# untitled.net
KiCad netlist of a schematic drawn in EAGLE
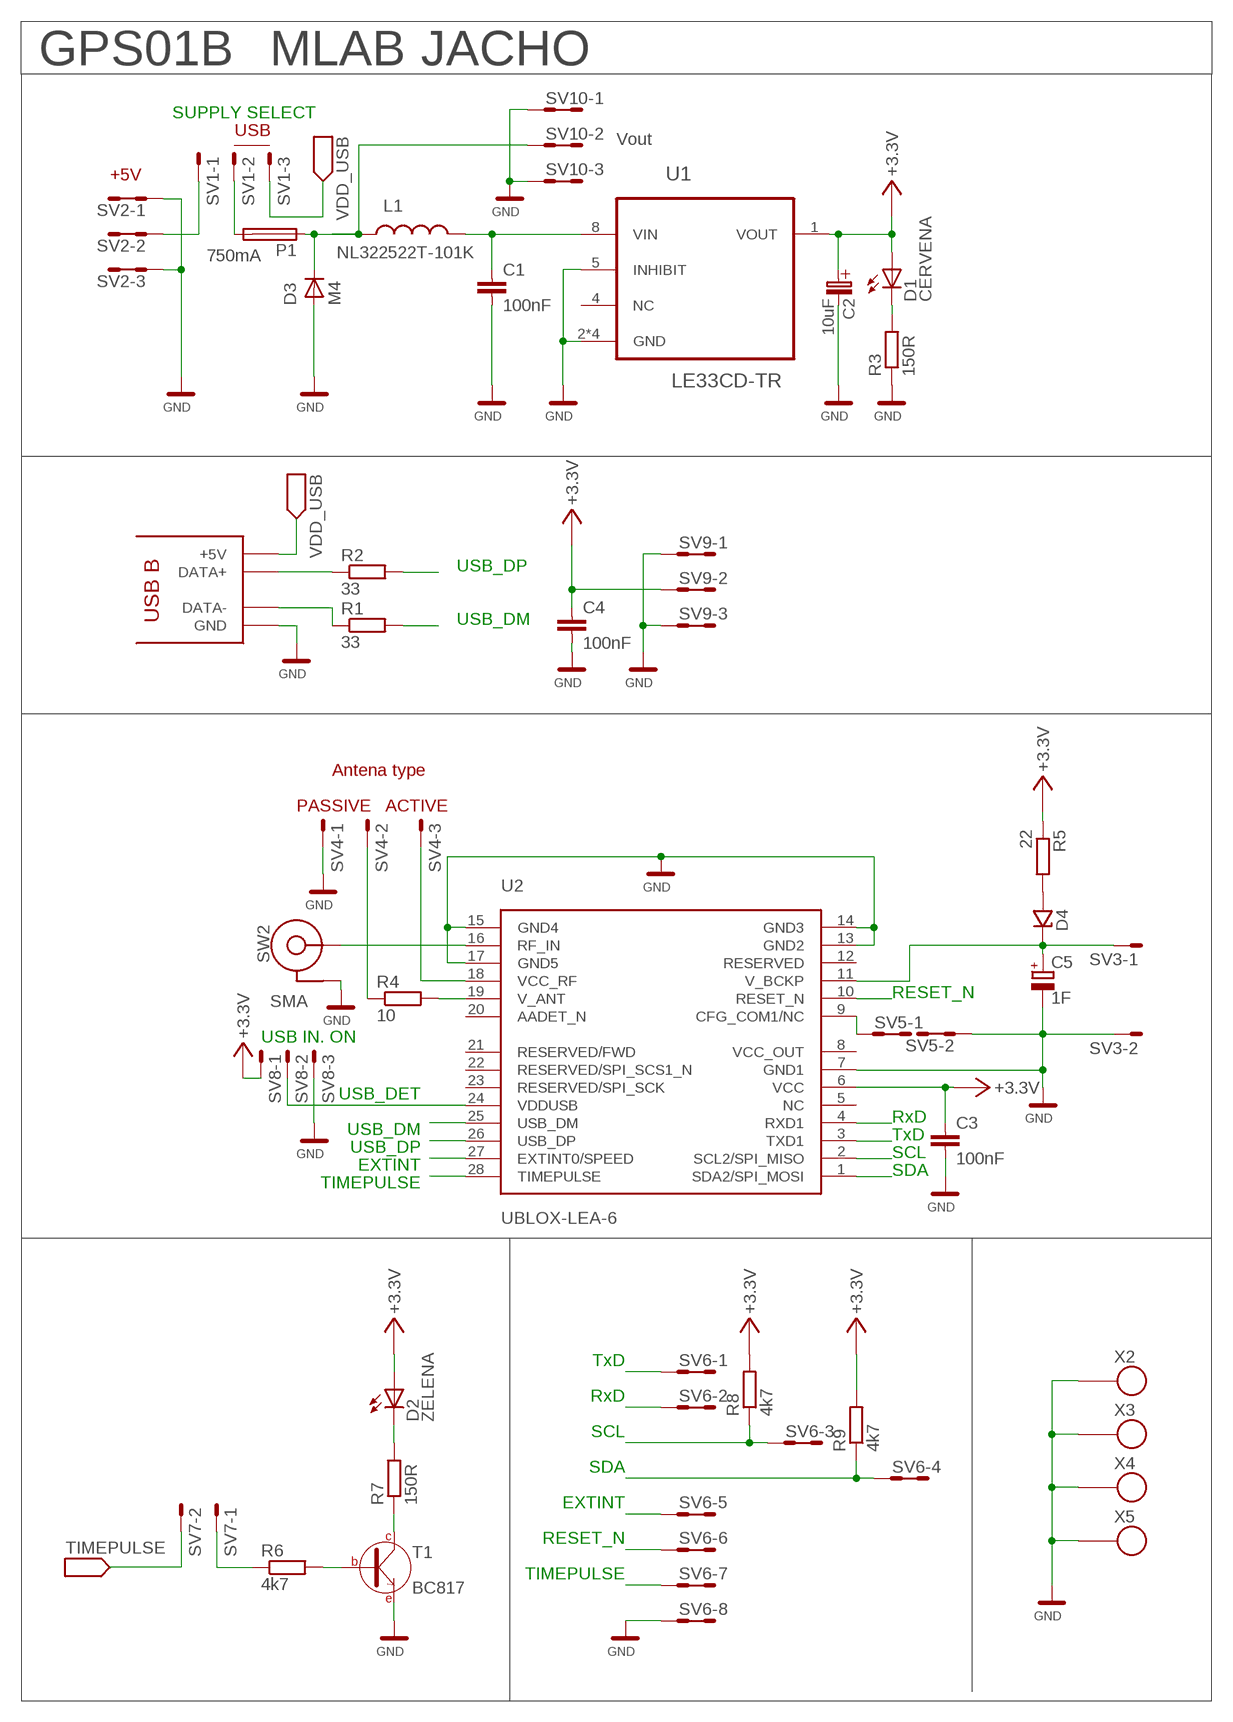
[diagram p0: schematic, sheet 1]

(export (version "E")
  (design (tool "Eeschema 10.0.6"))
  (components
    (comp (ref "C1")
      (value "100nF")
      (footprint "eagle-import:C0805")
      (libsource (lib "eagle-import") (part "C0805"))
    )
    (comp (ref "C2") (value "10uF") (footprint "eagle-import:B") (libsource (lib "eagle-import") (part "B")))
    (comp (ref "C3")
      (value "100nF")
      (footprint "eagle-import:C0805")
      (libsource (lib "eagle-import") (part "C0805"))
    )
    (comp (ref "C4")
      (value "100nF")
      (footprint "eagle-import:C0805")
      (libsource (lib "eagle-import") (part "C0805"))
    )
    (comp (ref "C5")
      (value "1F")
      (footprint "eagle-import:E3,5-8")
      (libsource (lib "eagle-import") (part "CPOL-EUE3.5-8"))
    )
    (comp (ref "D1")
      (value "CERVENA")
      (footprint "eagle-import:1206")
      (libsource (lib "eagle-import") (part "LED1206"))
    )
    (comp (ref "D2")
      (value "ZELENA")
      (footprint "eagle-import:1206")
      (libsource (lib "eagle-import") (part "LED1206"))
    )
    (comp (ref "D3")
      (value "M4")
      (footprint "eagle-import:SMA")
      (libsource (lib "eagle-import") (part "D-OB.SMA"))
    )
    (comp (ref "D4")
      (value "D-ZENEROVA")
      (footprint "eagle-import:MINIMELF")
      (libsource (lib "eagle-import") (part "D-ZENEROVA"))
    )
    (comp (ref "L1")
      (value "NL322522T-101K")
      (footprint "eagle-import:1210")
      (libsource (lib "eagle-import") (part "L1210"))
    )
    (comp (ref "P1")
      (value "750mA")
      (footprint "eagle-import:1812")
      (libsource (lib "eagle-import") (part "POJISTKA_1812"))
    )
    (comp (ref "R1")
      (value "33")
      (footprint "eagle-import:0805")
      (libsource (lib "eagle-import") (part "R0805"))
    )
    (comp (ref "R2")
      (value "33")
      (footprint "eagle-import:0805")
      (libsource (lib "eagle-import") (part "R0805"))
    )
    (comp (ref "R3")
      (value "150R")
      (footprint "eagle-import:0805")
      (libsource (lib "eagle-import") (part "R0805"))
    )
    (comp (ref "R4")
      (value "10")
      (footprint "eagle-import:0805")
      (libsource (lib "eagle-import") (part "R0805"))
    )
    (comp (ref "R5")
      (value "22")
      (footprint "eagle-import:0805")
      (libsource (lib "eagle-import") (part "R0805"))
    )
    (comp (ref "R6")
      (value "4k7")
      (footprint "eagle-import:0805")
      (libsource (lib "eagle-import") (part "R0805"))
    )
    (comp (ref "R7")
      (value "150R")
      (footprint "eagle-import:0805")
      (libsource (lib "eagle-import") (part "R0805"))
    )
    (comp (ref "R8")
      (value "4k7")
      (footprint "eagle-import:0805")
      (libsource (lib "eagle-import") (part "R0805"))
    )
    (comp (ref "R9")
      (value "4k7")
      (footprint "eagle-import:0805")
      (libsource (lib "eagle-import") (part "R0805"))
    )
    (comp (ref "SV1")
      (value "MA03-1")
      (footprint "eagle-import:MA03-1")
      (libsource (lib "eagle-import") (part "MA03-1"))
    )
    (comp (ref "SV2")
      (value "MA03-2")
      (footprint "eagle-import:MA03-2")
      (libsource (lib "eagle-import") (part "MA03-2"))
    )
    (comp (ref "SV3")
      (value "MA02-1")
      (footprint "eagle-import:MA02-1")
      (libsource (lib "eagle-import") (part "MA02-1"))
    )
    (comp (ref "SV4")
      (value "MA03-1")
      (footprint "eagle-import:MA03-1")
      (libsource (lib "eagle-import") (part "MA03-1"))
    )
    (comp (ref "SV5")
      (value "MA02-2")
      (footprint "eagle-import:MA02-2")
      (libsource (lib "eagle-import") (part "MA02-2"))
    )
    (comp (ref "SV6")
      (value "MA08-2")
      (footprint "eagle-import:MA08-2")
      (libsource (lib "eagle-import") (part "MA08-2"))
    )
    (comp (ref "SV7")
      (value "MA02-1")
      (footprint "eagle-import:MA02-1")
      (libsource (lib "eagle-import") (part "MA02-1"))
    )
    (comp (ref "SV8")
      (value "MA03-1")
      (footprint "eagle-import:MA03-1")
      (libsource (lib "eagle-import") (part "MA03-1"))
    )
    (comp (ref "SV9")
      (value "MA03-2")
      (footprint "eagle-import:MA03-2")
      (libsource (lib "eagle-import") (part "MA03-2"))
    )
    (comp (ref "SV10")
      (value "MA03-2")
      (footprint "eagle-import:MA03-2")
      (libsource (lib "eagle-import") (part "MA03-2"))
    )
    (comp (ref "SW2")
      (value "SMA")
      (footprint "eagle-import:SMA")
      (libsource (lib "eagle-import") (part "SMA"))
    )
    (comp (ref "T1")
      (value "BC817")
      (footprint "eagle-import:SOT23")
      (libsource (lib "eagle-import") (part "BC817"))
    )
    (comp (ref "U1")
      (value "LE33CD-TR")
      (footprint "eagle-import:SOIC127P600X175-8N")
      (libsource (lib "eagle-import") (part "LE33CD-TR"))
    )
    (comp (ref "U2")
      (value "UBLOX-LEA-6")
      (footprint "eagle-import:UBLOX-LEA-6")
      (libsource (lib "eagle-import") (part "UBLOX-LEA-6"))
    )
    (comp (ref "X1")
      (value "USB_B")
      (footprint "eagle-import:USB_B")
      (libsource (lib "eagle-import") (part "USB_B"))
    )
    (comp (ref "X2")
      (value "SROUB3M")
      (footprint "eagle-import:SROUB3M")
      (libsource (lib "eagle-import") (part "SROUB3M"))
    )
    (comp (ref "X3")
      (value "SROUB3M")
      (footprint "eagle-import:SROUB3M")
      (libsource (lib "eagle-import") (part "SROUB3M"))
    )
    (comp (ref "X4")
      (value "SROUB3M")
      (footprint "eagle-import:SROUB3M")
      (libsource (lib "eagle-import") (part "SROUB3M"))
    )
    (comp (ref "X5")
      (value "SROUB3M")
      (footprint "eagle-import:SROUB3M")
      (libsource (lib "eagle-import") (part "SROUB3M"))
    )
  )
  (nets
    (net (code "1") (name "+3.3V") (class "Default")
      (node (ref "C2") (pin "+") (pinfunction "C_EL+_+") (pintype "passive"))
      (node (ref "C3") (pin "1") (pinfunction "1_1") (pintype "passive"))
      (node (ref "C4") (pin "1") (pinfunction "1_1") (pintype "passive"))
      (node (ref "D1") (pin "A") (pinfunction "A_A") (pintype "passive"))
      (node (ref "D2") (pin "A") (pinfunction "A_A") (pintype "passive"))
      (node (ref "R5") (pin "1") (pinfunction "1_1") (pintype "passive"))
      (node (ref "R8") (pin "2") (pinfunction "2_2") (pintype "passive"))
      (node (ref "R9") (pin "2") (pinfunction "2_2") (pintype "passive"))
      (node (ref "SV8") (pin "1") (pinfunction "P$1_1") (pintype "passive"))
      (node (ref "SV9") (pin "3") (pinfunction "K_3") (pintype "passive"))
      (node (ref "SV9") (pin "4") (pinfunction "K_4") (pintype "passive"))
      (node (ref "U1") (pin "1") (pinfunction "VOUT_1") (pintype "output"))
      (node (ref "U2") (pin "6") (pinfunction "VCC_6") (pintype "bidirectional"))
    )
    (net (code "2") (name "/EXTINT") (class "Default")
      (node (ref "SV6") (pin "10") (pinfunction "K_10") (pintype "passive"))
      (node (ref "SV6") (pin "9") (pinfunction "K_9") (pintype "passive"))
      (node (ref "U2") (pin "27") (pinfunction "EXTINT0/SPEED_27") (pintype "bidirectional"))
    )
    (net (code "3") (name "/RESET_N") (class "Default")
      (node (ref "SV6") (pin "11") (pinfunction "K_11") (pintype "passive"))
      (node (ref "SV6") (pin "12") (pinfunction "K_12") (pintype "passive"))
      (node (ref "U2") (pin "10") (pinfunction "RESET_N_10") (pintype "bidirectional"))
    )
    (net (code "4") (name "/RXD") (class "Default")
      (node (ref "SV6") (pin "3") (pinfunction "K_3") (pintype "passive"))
      (node (ref "SV6") (pin "4") (pinfunction "K_4") (pintype "passive"))
      (node (ref "U2") (pin "4") (pinfunction "RXD1_4") (pintype "bidirectional"))
    )
    (net (code "5") (name "/SCL") (class "Default")
      (node (ref "R8") (pin "1") (pinfunction "1_1") (pintype "passive"))
      (node (ref "SV6") (pin "5") (pinfunction "K_5") (pintype "passive"))
      (node (ref "SV6") (pin "6") (pinfunction "K_6") (pintype "passive"))
      (node (ref "U2") (pin "2") (pinfunction "SCL2/SPI_MISO_2") (pintype "bidirectional"))
    )
    (net (code "6") (name "/SDA") (class "Default")
      (node (ref "R9") (pin "1") (pinfunction "1_1") (pintype "passive"))
      (node (ref "SV6") (pin "7") (pinfunction "K_7") (pintype "passive"))
      (node (ref "SV6") (pin "8") (pinfunction "K_8") (pintype "passive"))
      (node (ref "U2") (pin "1") (pinfunction "SDA2/SPI_MOSI_1") (pintype "bidirectional"))
    )
    (net (code "7") (name "/TIMEPULSE") (class "Default")
      (node (ref "SV6") (pin "13") (pinfunction "K_13") (pintype "passive"))
      (node (ref "SV6") (pin "14") (pinfunction "K_14") (pintype "passive"))
      (node (ref "SV7") (pin "2") (pinfunction "P$1_2") (pintype "passive"))
      (node (ref "U2") (pin "28") (pinfunction "TIMEPULSE_28") (pintype "bidirectional"))
    )
    (net (code "8") (name "/TXD") (class "Default")
      (node (ref "SV6") (pin "1") (pinfunction "K_1") (pintype "passive"))
      (node (ref "SV6") (pin "2") (pinfunction "K_2") (pintype "passive"))
      (node (ref "U2") (pin "3") (pinfunction "TXD1_3") (pintype "bidirectional"))
    )
    (net (code "9") (name "/USB_DM") (class "Default")
      (node (ref "R1") (pin "2") (pinfunction "2_2") (pintype "passive"))
      (node (ref "U2") (pin "25") (pinfunction "USB_DM_25") (pintype "bidirectional"))
    )
    (net (code "10") (name "/USB_DP") (class "Default")
      (node (ref "R2") (pin "2") (pinfunction "2_2") (pintype "passive"))
      (node (ref "U2") (pin "26") (pinfunction "USB_DP_26") (pintype "bidirectional"))
    )
    (net (code "11") (name "/VDD_USB") (class "Default")
      (node (ref "SV1") (pin "3") (pinfunction "P$1_3") (pintype "passive"))
      (node (ref "X1") (pin "1") (pinfunction "+5V_1") (pintype "bidirectional"))
    )
    (net (code "12") (name "GND") (class "Default")
      (node (ref "C1") (pin "2") (pinfunction "2_2") (pintype "passive"))
      (node (ref "C2") (pin "-") (pinfunction "C_EL-_-") (pintype "passive"))
      (node (ref "C3") (pin "2") (pinfunction "2_2") (pintype "passive"))
      (node (ref "C4") (pin "2") (pinfunction "2_2") (pintype "passive"))
      (node (ref "C5") (pin "-") (pinfunction "-_-") (pintype "passive"))
      (node (ref "D3") (pin "A") (pinfunction "A_A") (pintype "passive"))
      (node (ref "R3") (pin "1") (pinfunction "1_1") (pintype "passive"))
      (node (ref "SV10") (pin "1") (pinfunction "K_1") (pintype "passive"))
      (node (ref "SV10") (pin "2") (pinfunction "K_2") (pintype "passive"))
      (node (ref "SV10") (pin "5") (pinfunction "K_5") (pintype "passive"))
      (node (ref "SV10") (pin "6") (pinfunction "K_6") (pintype "passive"))
      (node (ref "SV2") (pin "1") (pinfunction "K_1") (pintype "passive"))
      (node (ref "SV2") (pin "2") (pinfunction "K_2") (pintype "passive"))
      (node (ref "SV2") (pin "5") (pinfunction "K_5") (pintype "passive"))
      (node (ref "SV2") (pin "6") (pinfunction "K_6") (pintype "passive"))
      (node (ref "SV3") (pin "2") (pinfunction "P$1_2") (pintype "passive"))
      (node (ref "SV4") (pin "1") (pinfunction "P$1_1") (pintype "passive"))
      (node (ref "SV5") (pin "3") (pinfunction "K_3") (pintype "passive"))
      (node (ref "SV5") (pin "4") (pinfunction "K_4") (pintype "passive"))
      (node (ref "SV6") (pin "15") (pinfunction "K_15") (pintype "passive"))
      (node (ref "SV6") (pin "16") (pinfunction "K_16") (pintype "passive"))
      (node (ref "SV8") (pin "3") (pinfunction "P$1_3") (pintype "passive"))
      (node (ref "SV9") (pin "1") (pinfunction "K_1") (pintype "passive"))
      (node (ref "SV9") (pin "2") (pinfunction "K_2") (pintype "passive"))
      (node (ref "SV9") (pin "5") (pinfunction "K_5") (pintype "passive"))
      (node (ref "SV9") (pin "6") (pinfunction "K_6") (pintype "passive"))
      (node (ref "SW2") (pin "-1") (pinfunction "-_-1") (pintype "passive"))
      (node (ref "SW2") (pin "-2") (pinfunction "-_-2") (pintype "passive"))
      (node (ref "SW2") (pin "-3") (pinfunction "-_-3") (pintype "passive"))
      (node (ref "SW2") (pin "-4") (pinfunction "-_-4") (pintype "passive"))
      (node (ref "T1") (pin "2") (pinfunction "E_2") (pintype "passive"))
      (node (ref "U1") (pin "2") (pinfunction "GND_2") (pintype "passive"))
      (node (ref "U1") (pin "3") (pinfunction "GND_3") (pintype "passive"))
      (node (ref "U1") (pin "5") (pinfunction "INHIBIT_5") (pintype "passive"))
      (node (ref "U1") (pin "6") (pinfunction "GND_6") (pintype "passive"))
      (node (ref "U1") (pin "7") (pinfunction "GND_7") (pintype "passive"))
      (node (ref "U2") (pin "13") (pinfunction "GND2_13") (pintype "bidirectional"))
      (node (ref "U2") (pin "14") (pinfunction "GND3_14") (pintype "bidirectional"))
      (node (ref "U2") (pin "15") (pinfunction "GND4_15") (pintype "bidirectional"))
      (node (ref "U2") (pin "17") (pinfunction "GND5_17") (pintype "bidirectional"))
      (node (ref "U2") (pin "7") (pinfunction "GND1_7") (pintype "bidirectional"))
      (node (ref "X1") (pin "4") (pinfunction "GND_4") (pintype "bidirectional"))
      (node (ref "X1") (pin "GND") (pinfunction "GND_GND") (pintype "bidirectional"))
      (node (ref "X1") (pin "GND2") (pinfunction "GND_GND2") (pintype "bidirectional"))
      (node (ref "X2") (pin "P$1") (pinfunction "P$1_P$1") (pintype "bidirectional"))
      (node (ref "X3") (pin "P$1") (pinfunction "P$1_P$1") (pintype "bidirectional"))
      (node (ref "X4") (pin "P$1") (pinfunction "P$1_P$1") (pintype "bidirectional"))
      (node (ref "X5") (pin "P$1") (pinfunction "P$1_P$1") (pintype "bidirectional"))
    )
    (net (code "13") (name "Net-(D1-C)") (class "Default")
      (node (ref "D1") (pin "K") (pinfunction "C_K") (pintype "passive"))
      (node (ref "R3") (pin "2") (pinfunction "2_2") (pintype "passive"))
    )
    (net (code "14") (name "Net-(D2-C)") (class "Default")
      (node (ref "D2") (pin "K") (pinfunction "C_K") (pintype "passive"))
      (node (ref "R7") (pin "2") (pinfunction "2_2") (pintype "passive"))
    )
    (net (code "15") (name "Net-(D3-C)") (class "Default")
      (node (ref "D3") (pin "K") (pinfunction "C_K") (pintype "passive"))
      (node (ref "L1") (pin "P$1") (pinfunction "1_P$1") (pintype "passive"))
      (node (ref "P1") (pin "1") (pinfunction "1_1") (pintype "passive"))
      (node (ref "SV10") (pin "3") (pinfunction "K_3") (pintype "passive"))
      (node (ref "SV10") (pin "4") (pinfunction "K_4") (pintype "passive"))
    )
    (net (code "16") (name "Net-(D4-K)") (class "Default")
      (node (ref "C5") (pin "+") (pinfunction "+_+") (pintype "passive"))
      (node (ref "D4") (pin "C") (pinfunction "K_C") (pintype "passive"))
      (node (ref "SV3") (pin "1") (pinfunction "P$1_1") (pintype "passive"))
      (node (ref "U2") (pin "11") (pinfunction "V_BCKP_11") (pintype "bidirectional"))
    )
    (net (code "17") (name "Net-(D4-PadA)") (class "Default")
      (node (ref "D4") (pin "A") (pinfunction "A_A") (pintype "passive"))
      (node (ref "R5") (pin "2") (pinfunction "2_2") (pintype "passive"))
    )
    (net (code "18") (name "Net-(L1-2)") (class "Default")
      (node (ref "C1") (pin "1") (pinfunction "1_1") (pintype "passive"))
      (node (ref "L1") (pin "P$2") (pinfunction "2_P$2") (pintype "passive"))
      (node (ref "U1") (pin "8") (pinfunction "VIN_8") (pintype "power_in"))
    )
    (net (code "19") (name "Net-(SV1A-P$1)") (class "Default")
      (node (ref "SV1") (pin "1") (pinfunction "P$1_1") (pintype "passive"))
      (node (ref "SV2") (pin "3") (pinfunction "K_3") (pintype "passive"))
      (node (ref "SV2") (pin "4") (pinfunction "K_4") (pintype "passive"))
    )
    (net (code "20") (name "Net-(SV1B-P$1)") (class "Default")
      (node (ref "P1") (pin "2") (pinfunction "2_2") (pintype "passive"))
      (node (ref "SV1") (pin "2") (pinfunction "P$1_2") (pintype "passive"))
    )
    (net (code "21") (name "Net-(SV4B-P$1)") (class "Default")
      (node (ref "R4") (pin "1") (pinfunction "1_1") (pintype "passive"))
      (node (ref "SV4") (pin "2") (pinfunction "P$1_2") (pintype "passive"))
    )
    (net (code "22") (name "Net-(SV4C-P$1)") (class "Default")
      (node (ref "SV4") (pin "3") (pinfunction "P$1_3") (pintype "passive"))
      (node (ref "U2") (pin "18") (pinfunction "VCC_RF_18") (pintype "bidirectional"))
    )
    (net (code "23") (name "Net-(SV7A-P$1)") (class "Default")
      (node (ref "R6") (pin "1") (pinfunction "1_1") (pintype "passive"))
      (node (ref "SV7") (pin "1") (pinfunction "P$1_1") (pintype "passive"))
    )
    (net (code "24") (name "Net-(SV8B-P$1)") (class "Default")
      (node (ref "SV8") (pin "2") (pinfunction "P$1_2") (pintype "passive"))
      (node (ref "U2") (pin "24") (pinfunction "VDDUSB_24") (pintype "bidirectional"))
    )
    (net (code "25") (name "Net-(T1-B)") (class "Default")
      (node (ref "R6") (pin "2") (pinfunction "2_2") (pintype "passive"))
      (node (ref "T1") (pin "1") (pinfunction "B_1") (pintype "passive"))
    )
    (net (code "26") (name "Net-(T1-C)") (class "Default")
      (node (ref "R7") (pin "1") (pinfunction "1_1") (pintype "passive"))
      (node (ref "T1") (pin "3") (pinfunction "C_3") (pintype "passive"))
    )
    (net (code "27") (name "Net-(U2-CFG_COM1{slash}NC)") (class "Default")
      (node (ref "SV5") (pin "1") (pinfunction "K_1") (pintype "passive"))
      (node (ref "SV5") (pin "2") (pinfunction "K_2") (pintype "passive"))
      (node (ref "U2") (pin "9") (pinfunction "CFG_COM1/NC_9") (pintype "bidirectional"))
    )
    (net (code "28") (name "Net-(U2-RF_IN)") (class "Default")
      (node (ref "SW2") (pin "+") (pinfunction "+_+") (pintype "passive"))
      (node (ref "U2") (pin "16") (pinfunction "RF_IN_16") (pintype "bidirectional"))
    )
    (net (code "29") (name "Net-(U2-V_ANT)") (class "Default")
      (node (ref "R4") (pin "2") (pinfunction "2_2") (pintype "passive"))
      (node (ref "U2") (pin "19") (pinfunction "V_ANT_19") (pintype "bidirectional"))
    )
    (net (code "30") (name "Net-(X1-DATA+)") (class "Default")
      (node (ref "R2") (pin "1") (pinfunction "1_1") (pintype "passive"))
      (node (ref "X1") (pin "3") (pinfunction "DATA+_3") (pintype "bidirectional"))
    )
    (net (code "31") (name "Net-(X1-DATA-)") (class "Default")
      (node (ref "R1") (pin "1") (pinfunction "1_1") (pintype "passive"))
      (node (ref "X1") (pin "2") (pinfunction "DATA-_2") (pintype "bidirectional"))
    )
    (net (code "32") (name "unconnected-(U1-NC-Pad4)") (class "Default")
      (node (ref "U1") (pin "4") (pinfunction "NC_4") (pintype "no_connect"))
    )
    (net (code "33") (name "unconnected-(U2-AADET_N-Pad20)") (class "Default")
      (node (ref "U2") (pin "20") (pinfunction "AADET_N_20") (pintype "bidirectional"))
    )
    (net (code "34") (name "unconnected-(U2-NC-Pad5)") (class "Default")
      (node (ref "U2") (pin "5") (pinfunction "NC_5") (pintype "bidirectional"))
    )
    (net (code "35") (name "unconnected-(U2-RESERVED-Pad12)") (class "Default")
      (node (ref "U2") (pin "12") (pinfunction "RESERVED_12") (pintype "bidirectional"))
    )
    (net (code "36") (name "unconnected-(U2-RESERVED{slash}FWD-Pad21)") (class "Default")
      (node (ref "U2") (pin "21") (pinfunction "RESERVED/FWD_21") (pintype "bidirectional"))
    )
    (net (code "37") (name "unconnected-(U2-RESERVED{slash}SPI_SCK-Pad23)") (class "Default")
      (node (ref "U2") (pin "23") (pinfunction "RESERVED/SPI_SCK_23") (pintype "bidirectional"))
    )
    (net (code "38") (name "unconnected-(U2-RESERVED{slash}SPI_SCS1_N-Pad22)") (class "Default")
      (node (ref "U2") (pin "22") (pinfunction "RESERVED/SPI_SCS1_N_22") (pintype "bidirectional"))
    )
    (net (code "39") (name "unconnected-(U2-VCC_OUT-Pad8)") (class "Default")
      (node (ref "U2") (pin "8") (pinfunction "VCC_OUT_8") (pintype "bidirectional"))
    )
  )
)
